# TTFT2.net
KiCad netlist of a schematic drawn in Altium Designer
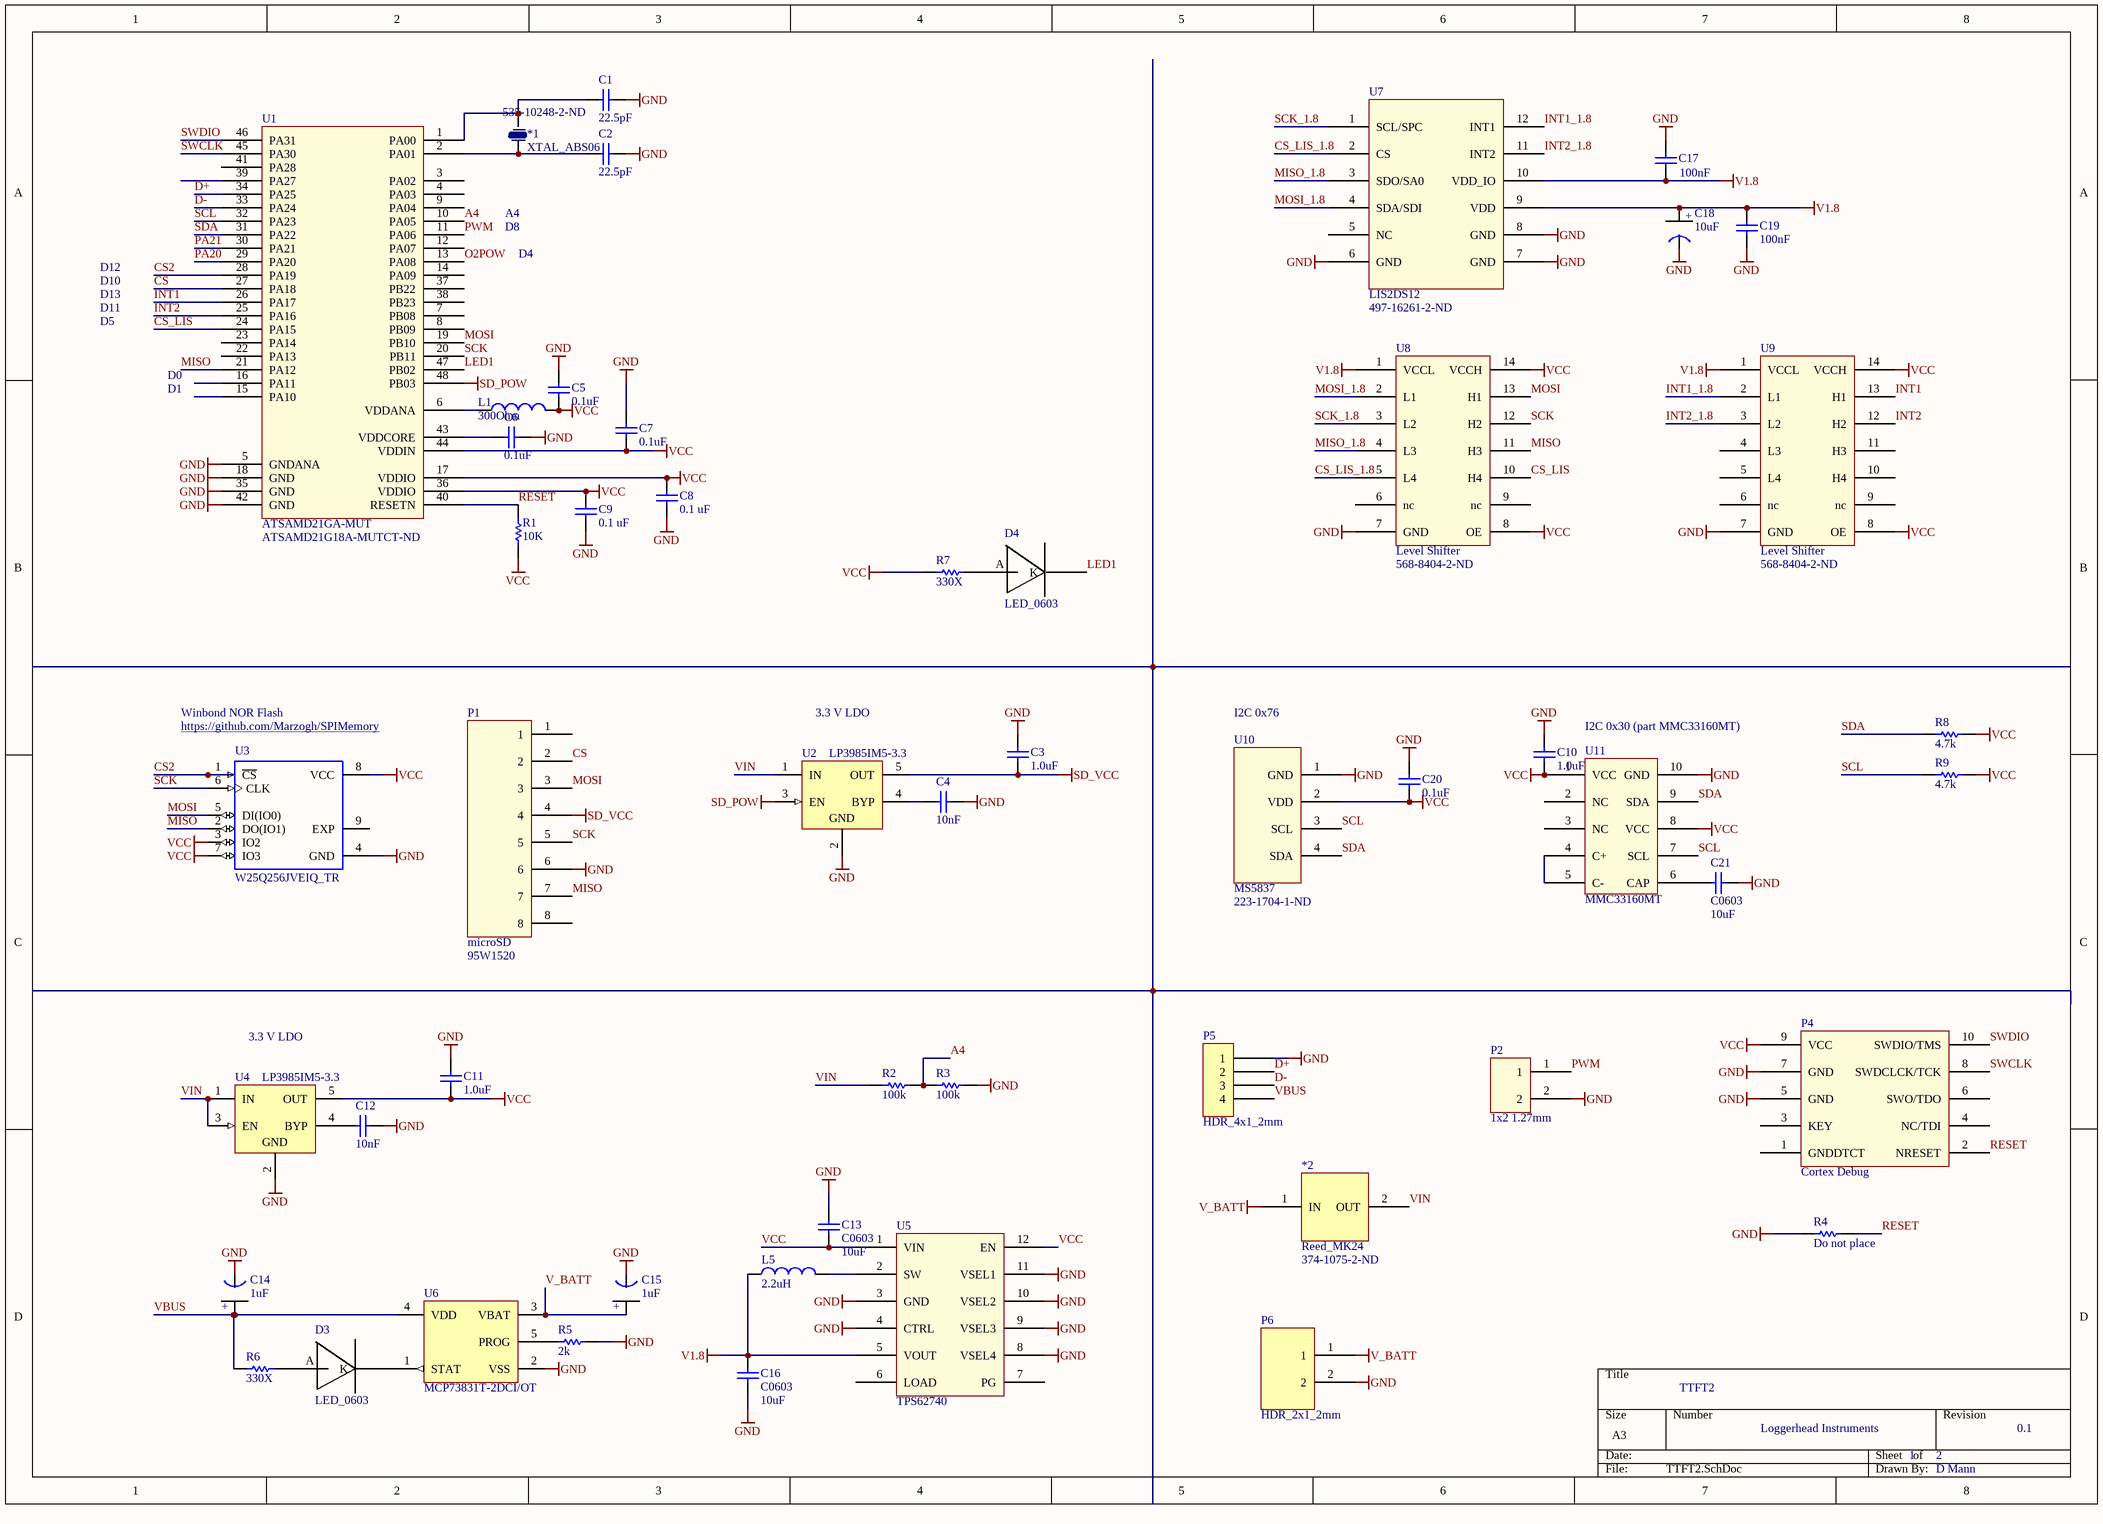
[diagram p0: TTFT2.SchDoc]

(export (version "E")
  (design (tool "Eeschema 10.0.6"))
  (components
    (comp (ref "*1")
      (value "XTAL_ABS06")
      (footprint "XTAL-ABS06")
      (fields (field (name "SUPPLIER PART NUMBER 1") "535-10248-2-ND"))
      (libsource (lib "Loggerhead") (part "XTAL_ABS06"))
    )
    (comp (ref "*2")
      (value "Reed_MK24")
      (footprint "Reed MK24-B-3")
      (fields (field (name "SUPPLIER PART NUMBER 1") "374-1075-2-ND"))
      (libsource (lib "Loggerhead") (part "Reed_MK24"))
    )
    (comp (ref "C1")
      (value "22.5pF")
      (footprint "0402")
      (description "Ceramic Chip Capacitor - Standard")
      (fields (field (name "PUBLISHER") "Altium Limited"))
      (libsource (lib "KEMET Chip Capacitor") (part "C0402"))
    )
    (comp (ref "C2")
      (value "22.5pF")
      (footprint "0402")
      (description "Ceramic Chip Capacitor - Standard")
      (fields (field (name "PUBLISHER") "Altium Limited"))
      (libsource (lib "KEMET Chip Capacitor") (part "C0402"))
    )
    (comp (ref "C3")
      (value "1.0uF")
      (footprint "0402")
      (description "Ceramic Chip Capacitor - Standard")
      (fields (field (name "PUBLISHER") "Altium Limited"))
      (libsource (lib "KEMET Chip Capacitor") (part "C0402"))
    )
    (comp (ref "C4")
      (value "10nF")
      (footprint "0402")
      (description "Ceramic Chip Capacitor - Standard")
      (fields (field (name "PUBLISHER") "Altium Limited"))
      (libsource (lib "KEMET Chip Capacitor") (part "C0402"))
    )
    (comp (ref "C5")
      (value "0.1uF")
      (footprint "0402")
      (description "Ceramic Chip Capacitor - Standard")
      (fields (field (name "PUBLISHER") "Altium Limited"))
      (libsource (lib "KEMET Chip Capacitor") (part "C0402"))
    )
    (comp (ref "C6")
      (value "0.1uF")
      (footprint "0402")
      (description "Ceramic Chip Capacitor - Standard")
      (fields (field (name "PUBLISHER") "Altium Limited"))
      (libsource (lib "KEMET Chip Capacitor") (part "C0402"))
    )
    (comp (ref "C7")
      (value "0.1uF")
      (footprint "0402")
      (description "Ceramic Chip Capacitor - Standard")
      (fields (field (name "PUBLISHER") "Altium Limited"))
      (libsource (lib "KEMET Chip Capacitor") (part "C0402"))
    )
    (comp (ref "C8")
      (value "0.1 uF")
      (footprint "0402")
      (description "Ceramic Chip Capacitor - Standard")
      (fields (field (name "PUBLISHER") "Altium Limited"))
      (libsource (lib "KEMET Chip Capacitor") (part "C0402"))
    )
    (comp (ref "C9")
      (value "0.1 uF")
      (footprint "0402")
      (description "Ceramic Chip Capacitor - Standard")
      (fields (field (name "PUBLISHER") "Altium Limited"))
      (libsource (lib "KEMET Chip Capacitor") (part "C0402"))
    )
    (comp (ref "C10")
      (value "1.0uF")
      (footprint "0402")
      (description "Ceramic Chip Capacitor - Standard")
      (fields (field (name "PUBLISHER") "Altium Limited"))
      (libsource (lib "KEMET Chip Capacitor") (part "C0402"))
    )
    (comp (ref "C11")
      (value "1.0uF")
      (footprint "0402")
      (description "Ceramic Chip Capacitor - Standard")
      (fields (field (name "PUBLISHER") "Altium Limited"))
      (libsource (lib "KEMET Chip Capacitor") (part "C0402"))
    )
    (comp (ref "C12")
      (value "10nF")
      (footprint "0402")
      (description "Ceramic Chip Capacitor - Standard")
      (fields (field (name "PUBLISHER") "Altium Limited"))
      (libsource (lib "KEMET Chip Capacitor") (part "C0402"))
    )
    (comp (ref "C13")
      (value "C0603")
      (footprint "0603")
      (description "Ceramic Chip Capacitor - Standard")
      (fields (field (name "ALTIUM_VALUE") "10uF") (field (name "PUBLISHER") "Altium Limited"))
      (libsource (lib "KEMET Chip Capacitor") (part "C0603"))
    )
    (comp (ref "C14") (value "1uF") (footprint "Tant0805") (libsource (lib "Loggerhead") (part "Tant0805")))
    (comp (ref "C15") (value "1uF") (footprint "Tant0805") (libsource (lib "Loggerhead") (part "Tant0805")))
    (comp (ref "C16")
      (value "C0603")
      (footprint "0603")
      (description "Ceramic Chip Capacitor - Standard")
      (fields (field (name "ALTIUM_VALUE") "10uF") (field (name "PUBLISHER") "Altium Limited"))
      (libsource (lib "KEMET Chip Capacitor") (part "C0603"))
    )
    (comp (ref "C17")
      (value "100nF")
      (footprint "0402")
      (description "Ceramic Chip Capacitor - Standard")
      (fields (field (name "PUBLISHER") "Altium Limited"))
      (libsource (lib "KEMET Chip Capacitor") (part "C0402"))
    )
    (comp (ref "C18") (value "10uF") (footprint "Tant0805") (libsource (lib "Loggerhead") (part "Tant0805")))
    (comp (ref "C19")
      (value "100nF")
      (footprint "0402")
      (description "Ceramic Chip Capacitor - Standard")
      (fields (field (name "PUBLISHER") "Altium Limited"))
      (libsource (lib "KEMET Chip Capacitor") (part "C0402"))
    )
    (comp (ref "C20")
      (value "0.1uF")
      (footprint "0402")
      (description "Ceramic Chip Capacitor - Standard")
      (fields (field (name "PUBLISHER") "Altium Limited"))
      (libsource (lib "KEMET Chip Capacitor") (part "C0402"))
    )
    (comp (ref "C21")
      (value "C0603")
      (footprint "0603")
      (description "Ceramic Chip Capacitor - Standard")
      (fields (field (name "ALTIUM_VALUE") "10uF") (field (name "PUBLISHER") "Altium Limited"))
      (libsource (lib "KEMET Chip Capacitor") (part "C0603"))
    )
    (comp (ref "D3")
      (value "LED_0603")
      (footprint "Diode0603")
      (libsource (lib "Loggerhead") (part "LED_0603"))
    )
    (comp (ref "D4")
      (value "LED_0603")
      (footprint "Diode0603")
      (libsource (lib "Loggerhead") (part "LED_0603"))
    )
    (comp (ref "L1")
      (value "300Ohm")
      (footprint "0805 (M2125) Ferrite")
      (description "Ferrite 25mOhm@DC,  60 Ohm@100MHz")
      (fields
        (field (name "CREATOR AND DATE") "Design Engineer's Name")
        (field (name "FOOTPRINT VERIFIED BY") "*")
        (field (name "SCHEMATIC VERIFIED BY") "*")
        (field (name "VENDOR INFO VERIFIED BY") "*")
      )
      (libsource (lib "Flanery") (part "Ferrite 0805(M2125) 3A"))
    )
    (comp (ref "L5")
      (value "2.2uH")
      (footprint "Inductor KLZ1608AHR")
      (libsource (lib "Loggerhead") (part "Inductor KLZ1608"))
    )
    (comp (ref "P1")
      (value "microSD")
      (footprint "Molex microSD")
      (fields (field (name "SUPPLIER PART NUMBER 1") "95W1520"))
      (libsource (lib "Loggerhead") (part "microSD Molex tiny"))
    )
    (comp (ref "P2")
      (value "1x2 1.27mm")
      (footprint "Header1x2 1.27mm")
      (libsource (lib "Loggerhead") (part "Header 1x2 1.27mm"))
    )
    (comp (ref "P4")
      (value "Cortex Debug")
      (footprint "Header_2x5_50mil")
      (libsource (lib "Loggerhead") (part "CortexDebug"))
    )
    (comp (ref "P5")
      (value "HDR_4x1_2mm")
      (footprint "Hdr_4x1_2mm")
      (libsource (lib "Loggerhead") (part "HDR_4x1_2mm"))
    )
    (comp (ref "P6")
      (value "HDR_2x1_2mm")
      (footprint "HDR_2x1_2mm")
      (libsource (lib "Loggerhead") (part "HDR_2x1_2mm"))
    )
    (comp (ref "R1")
      (value "10K")
      (footprint "3-0603")
      (fields (field (name "PUBLISHER") "Altium Limited"))
      (libsource (lib "Panasonic Resistor") (part "ERJ3RK"))
    )
    (comp (ref "R2")
      (value "100k")
      (footprint "3-0603")
      (fields (field (name "PUBLISHER") "Altium Limited"))
      (libsource (lib "Panasonic Resistor") (part "ERJ3RK"))
    )
    (comp (ref "R3")
      (value "100k")
      (footprint "3-0603")
      (fields (field (name "PUBLISHER") "Altium Limited"))
      (libsource (lib "Panasonic Resistor") (part "ERJ3RK"))
    )
    (comp (ref "R4")
      (value "Do not place")
      (footprint "3-0603")
      (fields (field (name "PUBLISHER") "Altium Limited"))
      (libsource (lib "Panasonic Resistor") (part "ERJ3RK"))
    )
    (comp (ref "R5")
      (value "2k")
      (footprint "3-0603")
      (fields (field (name "PUBLISHER") "Altium Limited"))
      (libsource (lib "Panasonic Resistor") (part "ERJ3RK"))
    )
    (comp (ref "R6")
      (value "330X")
      (footprint "3-0603")
      (fields (field (name "PUBLISHER") "Altium Limited"))
      (libsource (lib "Panasonic Resistor") (part "ERJ3RK"))
    )
    (comp (ref "R7")
      (value "330X")
      (footprint "3-0603")
      (fields (field (name "PUBLISHER") "Altium Limited"))
      (libsource (lib "Panasonic Resistor") (part "ERJ3RK"))
    )
    (comp (ref "R8")
      (value "4.7k")
      (footprint "3-0603")
      (fields (field (name "PUBLISHER") "Altium Limited"))
      (libsource (lib "Panasonic Resistor") (part "ERJ3RK"))
    )
    (comp (ref "R9")
      (value "4.7k")
      (footprint "3-0603")
      (fields (field (name "PUBLISHER") "Altium Limited"))
      (libsource (lib "Panasonic Resistor") (part "ERJ3RK"))
    )
    (comp (ref "U1")
      (value "ATSAMD21GA-MUT")
      (footprint "QFN127P600-8N")
      (fields (field (name "SUPPLIER PART NUMBER 1") "ATSAMD21G18A-MUTCT-ND"))
      (libsource (lib "Loggerhead") (part "ATSAMD21G18"))
    )
    (comp (ref "U2")
      (value "LP3985IM5-3.3")
      (footprint "MF05A_N")
      (description "Micropower, 150mA Low-Noise Ultra Low-Dropout CMOS Voltage Regulator, 5-pin SOT-23")
      (fields
        (field (name "MANUFACTURER") "National Semiconductor")
        (field (name "PUBLISHER") "Altium Limited")
      )
      (libsource (lib "NSC LDO") (part "LP3985IM5-3.3"))
    )
    (comp (ref "U3")
      (value "W25Q256JVEIQ_TR")
      (footprint "*SON127P800X600X80-9N")
      (description "Ic Flash 256mbit 104mhz 8wson")
      (fields (field (name "MF") "Winbond") (field (name "MP") "W25Q256JVEIQ TR"))
      (libsource (lib "W25Q256JVEIQ_TR") (part "W25Q256JVEIQ_TR"))
    )
    (comp (ref "U4")
      (value "LP3985IM5-3.3")
      (footprint "MF05A_N")
      (description "Micropower, 150mA Low-Noise Ultra Low-Dropout CMOS Voltage Regulator, 5-pin SOT-23")
      (fields
        (field (name "MANUFACTURER") "National Semiconductor")
        (field (name "PUBLISHER") "Altium Limited")
      )
      (libsource (lib "NSC LDO") (part "LP3985IM5-3.3"))
    )
    (comp (ref "U5")
      (value "TPS62740")
      (footprint "TPS6274x")
      (libsource (lib "Loggerhead") (part "TPS6274x"))
    )
    (comp (ref "U6")
      (value "MCP73831T-2DCI/OT")
      (footprint "SOT-23-OT5_N")
      (libsource (lib "Microchip Power Management Battery Management") (part "MCP73831T-2DCI/OT"))
    )
    (comp (ref "U7")
      (value "LIS2DS12")
      (footprint "LGA-12")
      (fields (field (name "SUPPLIER PART NUMBER 1") "497-16261-2-ND"))
      (libsource (lib "Loggerhead") (part "LIS2DS12"))
    )
    (comp (ref "U8")
      (value "Level Shifter")
      (footprint "DHVQFN14")
      (description "Voltage level translator")
      (fields (field (name "SUPPLIER PART NUMBER 1") "568-8404-2-ND"))
      (libsource (lib "Loggerhead") (part "NTB0104"))
    )
    (comp (ref "U9")
      (value "Level Shifter")
      (footprint "DHVQFN14")
      (description "Voltage level translator")
      (fields (field (name "SUPPLIER PART NUMBER 1") "568-8404-2-ND"))
      (libsource (lib "Loggerhead") (part "NTB0104"))
    )
    (comp (ref "U10")
      (value "MS5837")
      (footprint "MS5837")
      (description "Pressure/Temp")
      (fields (field (name "SUPPLIER PART NUMBER 1") "223-1704-1-ND"))
      (libsource (lib "Loggerhead") (part "MS5837"))
    )
    (comp (ref "U11")
      (value "MMC33160MT")
      (footprint "MMC33160MT")
      (libsource (lib "Loggerhead") (part "MMC33160MT"))
    )
  )
  (nets
    (net (code "1") (name "/A4") (class "Default")
      (node (ref "R2") (pin "1") (pinfunction "1_1") (pintype "passive"))
      (node (ref "R3") (pin "2") (pinfunction "2_2") (pintype "passive"))
      (node (ref "U1") (pin "10") (pinfunction "PA05_10") (pintype "passive"))
    )
    (net (code "2") (name "/CS") (class "Default")
      (node (ref "P1") (pin "2") (pinfunction "2_2") (pintype "passive"))
      (node (ref "U1") (pin "27") (pinfunction "PA18_27") (pintype "passive"))
    )
    (net (code "3") (name "/CS2") (class "Default")
      (node (ref "U1") (pin "28") (pinfunction "PA19_28") (pintype "passive"))
      (node (ref "U3") (pin "1") (pinfunction "~{CS}_1") (pintype "input"))
    )
    (net (code "4") (name "/CS_LIS") (class "Default")
      (node (ref "U1") (pin "24") (pinfunction "PA15_24") (pintype "passive"))
      (node (ref "U8") (pin "10") (pinfunction "H4_10") (pintype "passive"))
    )
    (net (code "5") (name "/CS_LIS_1.8") (class "Default")
      (node (ref "U7") (pin "2") (pinfunction "CS_2") (pintype "passive"))
      (node (ref "U8") (pin "5") (pinfunction "L4_5") (pintype "passive"))
    )
    (net (code "6") (name "/D+") (class "Default")
      (node (ref "P5") (pin "2") (pinfunction "2_2") (pintype "passive"))
      (node (ref "U1") (pin "34") (pinfunction "PA25_34") (pintype "passive"))
    )
    (net (code "7") (name "/D-") (class "Default")
      (node (ref "P5") (pin "3") (pinfunction "3_3") (pintype "passive"))
      (node (ref "U1") (pin "33") (pinfunction "PA24_33") (pintype "passive"))
    )
    (net (code "8") (name "/INT1") (class "Default")
      (node (ref "U1") (pin "26") (pinfunction "PA17_26") (pintype "passive"))
      (node (ref "U9") (pin "13") (pinfunction "H1_13") (pintype "passive"))
    )
    (net (code "9") (name "/INT1_1.8") (class "Default")
      (node (ref "U7") (pin "12") (pinfunction "INT1_12") (pintype "passive"))
      (node (ref "U9") (pin "2") (pinfunction "L1_2") (pintype "passive"))
    )
    (net (code "10") (name "/INT2") (class "Default")
      (node (ref "U1") (pin "25") (pinfunction "PA16_25") (pintype "passive"))
      (node (ref "U9") (pin "12") (pinfunction "H2_12") (pintype "passive"))
    )
    (net (code "11") (name "/INT2_1.8") (class "Default")
      (node (ref "U7") (pin "11") (pinfunction "INT2_11") (pintype "passive"))
      (node (ref "U9") (pin "3") (pinfunction "L2_3") (pintype "passive"))
    )
    (net (code "12") (name "/LED1") (class "Default")
      (node (ref "D4") (pin "K") (pinfunction "K_K") (pintype "passive"))
      (node (ref "U1") (pin "47") (pinfunction "PB02_47") (pintype "passive"))
    )
    (net (code "13") (name "/MISO") (class "Default")
      (node (ref "P1") (pin "7") (pinfunction "7_7") (pintype "passive"))
      (node (ref "U1") (pin "21") (pinfunction "PA12_21") (pintype "passive"))
      (node (ref "U3") (pin "2") (pinfunction "DO(IO1)_2") (pintype "bidirectional"))
      (node (ref "U8") (pin "11") (pinfunction "H3_11") (pintype "passive"))
    )
    (net (code "14") (name "/MISO_1.8") (class "Default")
      (node (ref "U7") (pin "3") (pinfunction "SDO/SA0_3") (pintype "passive"))
      (node (ref "U8") (pin "4") (pinfunction "L3_4") (pintype "passive"))
    )
    (net (code "15") (name "/MOSI") (class "Default")
      (node (ref "P1") (pin "3") (pinfunction "3_3") (pintype "passive"))
      (node (ref "U1") (pin "19") (pinfunction "PB10_19") (pintype "passive"))
      (node (ref "U3") (pin "5") (pinfunction "DI(IO0)_5") (pintype "bidirectional"))
      (node (ref "U8") (pin "13") (pinfunction "H1_13") (pintype "passive"))
    )
    (net (code "16") (name "/MOSI_1.8") (class "Default")
      (node (ref "U7") (pin "4") (pinfunction "SDA/SDI_4") (pintype "passive"))
      (node (ref "U8") (pin "2") (pinfunction "L1_2") (pintype "passive"))
    )
    (net (code "17") (name "/O2POW") (class "Default")
      (node (ref "U1") (pin "13") (pinfunction "PA08_13") (pintype "passive"))
    )
    (net (code "18") (name "/PA20") (class "Default")
      (node (ref "U1") (pin "29") (pinfunction "PA20_29") (pintype "passive"))
    )
    (net (code "19") (name "/PA21") (class "Default")
      (node (ref "U1") (pin "30") (pinfunction "PA21_30") (pintype "passive"))
    )
    (net (code "20") (name "/PWM") (class "Default")
      (node (ref "P2") (pin "1") (pinfunction "1_1") (pintype "passive"))
      (node (ref "U1") (pin "11") (pinfunction "PA06_11") (pintype "passive"))
    )
    (net (code "21") (name "/RESET") (class "Default")
      (node (ref "P4") (pin "2") (pinfunction "NRESET_2") (pintype "passive"))
      (node (ref "R1") (pin "2") (pinfunction "2_2") (pintype "passive"))
      (node (ref "R4") (pin "1") (pinfunction "1_1") (pintype "passive"))
      (node (ref "U1") (pin "40") (pinfunction "RESETN_40") (pintype "passive"))
    )
    (net (code "22") (name "/SCK") (class "Default")
      (node (ref "P1") (pin "5") (pinfunction "5_5") (pintype "passive"))
      (node (ref "U1") (pin "20") (pinfunction "PB11_20") (pintype "passive"))
      (node (ref "U3") (pin "6") (pinfunction "CLK_6") (pintype "input"))
      (node (ref "U8") (pin "12") (pinfunction "H2_12") (pintype "passive"))
    )
    (net (code "23") (name "/SCK_1.8") (class "Default")
      (node (ref "U7") (pin "1") (pinfunction "SCL/SPC_1") (pintype "passive"))
      (node (ref "U8") (pin "3") (pinfunction "L2_3") (pintype "passive"))
    )
    (net (code "24") (name "/SCL") (class "Default")
      (node (ref "R9") (pin "1") (pinfunction "1_1") (pintype "passive"))
      (node (ref "U1") (pin "32") (pinfunction "PA23_32") (pintype "passive"))
      (node (ref "U10") (pin "3") (pinfunction "SCL_3") (pintype "passive"))
      (node (ref "U11") (pin "7") (pinfunction "SCL_7") (pintype "passive"))
    )
    (net (code "25") (name "/SDA") (class "Default")
      (node (ref "R8") (pin "2") (pinfunction "2_2") (pintype "passive"))
      (node (ref "U1") (pin "31") (pinfunction "PA22_31") (pintype "passive"))
      (node (ref "U10") (pin "4") (pinfunction "SDA_4") (pintype "passive"))
      (node (ref "U11") (pin "9") (pinfunction "SDA_9") (pintype "passive"))
    )
    (net (code "26") (name "/SWCLK") (class "Default")
      (node (ref "P4") (pin "8") (pinfunction "SWDCLCK/TCK_8") (pintype "passive"))
      (node (ref "U1") (pin "45") (pinfunction "PA30_45") (pintype "passive"))
    )
    (net (code "27") (name "/SWDIO") (class "Default")
      (node (ref "P4") (pin "10") (pinfunction "SWDIO/TMS_10") (pintype "passive"))
      (node (ref "U1") (pin "46") (pinfunction "PA31_46") (pintype "passive"))
    )
    (net (code "28") (name "/VBUS") (class "Default")
      (node (ref "C14") (pin "2") (pinfunction "+_2") (pintype "passive"))
      (node (ref "P5") (pin "4") (pinfunction "4_4") (pintype "passive"))
      (node (ref "R6") (pin "1") (pinfunction "1_1") (pintype "passive"))
      (node (ref "U6") (pin "4") (pinfunction "VDD_4") (pintype "power_in"))
    )
    (net (code "29") (name "/VIN") (class "Default")
      (node (ref "*2") (pin "2") (pinfunction "OUT_2") (pintype "passive"))
      (node (ref "R2") (pin "2") (pinfunction "2_2") (pintype "passive"))
      (node (ref "U2") (pin "1") (pinfunction "IN_1") (pintype "power_in"))
      (node (ref "U4") (pin "1") (pinfunction "IN_1") (pintype "power_in"))
      (node (ref "U4") (pin "3") (pinfunction "EN_3") (pintype "input"))
    )
    (net (code "30") (name "GND") (class "Default")
      (node (ref "C1") (pin "1") (pinfunction "1_1") (pintype "passive"))
      (node (ref "C10") (pin "2") (pinfunction "2_2") (pintype "passive"))
      (node (ref "C11") (pin "2") (pinfunction "2_2") (pintype "passive"))
      (node (ref "C12") (pin "1") (pinfunction "1_1") (pintype "passive"))
      (node (ref "C13") (pin "2") (pinfunction "2_2") (pintype "passive"))
      (node (ref "C14") (pin "1") (pinfunction "GND_1") (pintype "passive"))
      (node (ref "C15") (pin "1") (pinfunction "GND_1") (pintype "passive"))
      (node (ref "C16") (pin "1") (pinfunction "1_1") (pintype "passive"))
      (node (ref "C17") (pin "2") (pinfunction "2_2") (pintype "passive"))
      (node (ref "C18") (pin "1") (pinfunction "GND_1") (pintype "passive"))
      (node (ref "C19") (pin "2") (pinfunction "2_2") (pintype "passive"))
      (node (ref "C2") (pin "1") (pinfunction "1_1") (pintype "passive"))
      (node (ref "C20") (pin "2") (pinfunction "2_2") (pintype "passive"))
      (node (ref "C21") (pin "1") (pinfunction "1_1") (pintype "passive"))
      (node (ref "C3") (pin "2") (pinfunction "2_2") (pintype "passive"))
      (node (ref "C4") (pin "1") (pinfunction "1_1") (pintype "passive"))
      (node (ref "C5") (pin "2") (pinfunction "2_2") (pintype "passive"))
      (node (ref "C6") (pin "2") (pinfunction "2_2") (pintype "passive"))
      (node (ref "C7") (pin "2") (pinfunction "2_2") (pintype "passive"))
      (node (ref "C8") (pin "2") (pinfunction "2_2") (pintype "passive"))
      (node (ref "C9") (pin "2") (pinfunction "2_2") (pintype "passive"))
      (node (ref "P1") (pin "6") (pinfunction "6_6") (pintype "passive"))
      (node (ref "P2") (pin "2") (pinfunction "2_2") (pintype "passive"))
      (node (ref "P4") (pin "5") (pinfunction "GND_5") (pintype "passive"))
      (node (ref "P4") (pin "7") (pinfunction "GND_7") (pintype "passive"))
      (node (ref "P5") (pin "1") (pinfunction "1_1") (pintype "passive"))
      (node (ref "P6") (pin "2") (pinfunction "2_2") (pintype "passive"))
      (node (ref "R3") (pin "1") (pinfunction "1_1") (pintype "passive"))
      (node (ref "R4") (pin "2") (pinfunction "2_2") (pintype "passive"))
      (node (ref "R5") (pin "1") (pinfunction "1_1") (pintype "passive"))
      (node (ref "U1") (pin "18") (pinfunction "GND_18") (pintype "passive"))
      (node (ref "U1") (pin "35") (pinfunction "GND_35") (pintype "passive"))
      (node (ref "U1") (pin "42") (pinfunction "GND_42") (pintype "passive"))
      (node (ref "U1") (pin "5") (pinfunction "GNDANA_5") (pintype "passive"))
      (node (ref "U10") (pin "1") (pinfunction "GND_1") (pintype "passive"))
      (node (ref "U11") (pin "10") (pinfunction "GND_10") (pintype "passive"))
      (node (ref "U2") (pin "2") (pinfunction "GND_2") (pintype "power_in"))
      (node (ref "U3") (pin "4") (pinfunction "GND_4") (pintype "power_in"))
      (node (ref "U4") (pin "2") (pinfunction "GND_2") (pintype "power_in"))
      (node (ref "U5") (pin "10") (pinfunction "VSEL2_10") (pintype "passive"))
      (node (ref "U5") (pin "11") (pinfunction "VSEL1_11") (pintype "passive"))
      (node (ref "U5") (pin "3") (pinfunction "GND_3") (pintype "passive"))
      (node (ref "U5") (pin "4") (pinfunction "CTRL_4") (pintype "passive"))
      (node (ref "U5") (pin "8") (pinfunction "VSEL4_8") (pintype "passive"))
      (node (ref "U5") (pin "9") (pinfunction "VSEL3_9") (pintype "passive"))
      (node (ref "U6") (pin "2") (pinfunction "VSS_2") (pintype "power_in"))
      (node (ref "U7") (pin "6") (pinfunction "GND_6") (pintype "passive"))
      (node (ref "U7") (pin "7") (pinfunction "GND_7") (pintype "passive"))
      (node (ref "U7") (pin "8") (pinfunction "GND_8") (pintype "passive"))
      (node (ref "U8") (pin "7") (pinfunction "GND_7") (pintype "passive"))
      (node (ref "U9") (pin "7") (pinfunction "GND_7") (pintype "passive"))
    )
    (net (code "31") (name "Net-(D3-PadA)") (class "Default")
      (node (ref "D3") (pin "A") (pinfunction "A_A") (pintype "passive"))
      (node (ref "R6") (pin "2") (pinfunction "2_2") (pintype "passive"))
    )
    (net (code "32") (name "Net-(D4-PadA)") (class "Default")
      (node (ref "D4") (pin "A") (pinfunction "A_A") (pintype "passive"))
      (node (ref "R7") (pin "2") (pinfunction "2_2") (pintype "passive"))
    )
    (net (code "33") (name "Net-(U1-PA00)") (class "Default")
      (node (ref "*1") (pin "2") (pinfunction "2_2") (pintype "passive"))
      (node (ref "C1") (pin "2") (pinfunction "2_2") (pintype "passive"))
      (node (ref "U1") (pin "1") (pinfunction "PA00_1") (pintype "passive"))
    )
    (net (code "34") (name "Net-(U1-PA01)") (class "Default")
      (node (ref "*1") (pin "1") (pinfunction "1_1") (pintype "passive"))
      (node (ref "C2") (pin "2") (pinfunction "2_2") (pintype "passive"))
      (node (ref "U1") (pin "2") (pinfunction "PA01_2") (pintype "passive"))
    )
    (net (code "35") (name "Net-(U1-VDDANA)") (class "Default")
      (node (ref "L1") (pin "1") (pinfunction "1_1") (pintype "passive"))
      (node (ref "U1") (pin "6") (pinfunction "VDDANA_6") (pintype "passive"))
    )
    (net (code "36") (name "Net-(U1-VDDCORE)") (class "Default")
      (node (ref "C6") (pin "1") (pinfunction "1_1") (pintype "passive"))
      (node (ref "U1") (pin "43") (pinfunction "VDDCORE_43") (pintype "passive"))
    )
    (net (code "37") (name "Net-(U2-BYP)") (class "Default")
      (node (ref "C4") (pin "2") (pinfunction "2_2") (pintype "passive"))
      (node (ref "U2") (pin "4") (pinfunction "BYP_4") (pintype "passive"))
    )
    (net (code "38") (name "Net-(U4-BYP)") (class "Default")
      (node (ref "C12") (pin "2") (pinfunction "2_2") (pintype "passive"))
      (node (ref "U4") (pin "4") (pinfunction "BYP_4") (pintype "passive"))
    )
    (net (code "39") (name "Net-(U5-SW)") (class "Default")
      (node (ref "L5") (pin "2") (pinfunction "2_2") (pintype "passive"))
      (node (ref "U5") (pin "2") (pinfunction "SW_2") (pintype "passive"))
    )
    (net (code "40") (name "Net-(U6-PROG)") (class "Default")
      (node (ref "R5") (pin "2") (pinfunction "2_2") (pintype "passive"))
      (node (ref "U6") (pin "5") (pinfunction "PROG_5") (pintype "passive"))
    )
    (net (code "41") (name "Net-(U6-STAT)") (class "Default")
      (node (ref "D3") (pin "K") (pinfunction "K_K") (pintype "passive"))
      (node (ref "U6") (pin "1") (pinfunction "STAT_1") (pintype "output"))
    )
    (net (code "42") (name "Net-(U11-C+)") (class "Default")
      (node (ref "U11") (pin "4") (pinfunction "C+_4") (pintype "passive"))
      (node (ref "U11") (pin "5") (pinfunction "C-_5") (pintype "passive"))
    )
    (net (code "43") (name "Net-(U11-CAP)") (class "Default")
      (node (ref "C21") (pin "2") (pinfunction "2_2") (pintype "passive"))
      (node (ref "U11") (pin "6") (pinfunction "CAP_6") (pintype "passive"))
    )
    (net (code "44") (name "SD_POW") (class "Default")
      (node (ref "U1") (pin "48") (pinfunction "PB03_48") (pintype "passive"))
      (node (ref "U2") (pin "3") (pinfunction "EN_3") (pintype "input"))
    )
    (net (code "45") (name "SD_VCC") (class "Default")
      (node (ref "C3") (pin "1") (pinfunction "1_1") (pintype "passive"))
      (node (ref "P1") (pin "4") (pinfunction "4_4") (pintype "passive"))
      (node (ref "U2") (pin "5") (pinfunction "OUT_5") (pintype "power_in"))
    )
    (net (code "46") (name "V1.8") (class "Default")
      (node (ref "C16") (pin "2") (pinfunction "2_2") (pintype "passive"))
      (node (ref "C17") (pin "1") (pinfunction "1_1") (pintype "passive"))
      (node (ref "C18") (pin "2") (pinfunction "+_2") (pintype "passive"))
      (node (ref "C19") (pin "1") (pinfunction "1_1") (pintype "passive"))
      (node (ref "L5") (pin "1") (pinfunction "1_1") (pintype "passive"))
      (node (ref "U5") (pin "5") (pinfunction "VOUT_5") (pintype "passive"))
      (node (ref "U7") (pin "10") (pinfunction "VDD_IO_10") (pintype "passive"))
      (node (ref "U7") (pin "9") (pinfunction "VDD_9") (pintype "passive"))
      (node (ref "U8") (pin "1") (pinfunction "VCCL_1") (pintype "passive"))
      (node (ref "U9") (pin "1") (pinfunction "VCCL_1") (pintype "passive"))
    )
    (net (code "47") (name "VCC") (class "Default")
      (node (ref "C10") (pin "1") (pinfunction "1_1") (pintype "passive"))
      (node (ref "C11") (pin "1") (pinfunction "1_1") (pintype "passive"))
      (node (ref "C13") (pin "1") (pinfunction "1_1") (pintype "passive"))
      (node (ref "C20") (pin "1") (pinfunction "1_1") (pintype "passive"))
      (node (ref "C5") (pin "1") (pinfunction "1_1") (pintype "passive"))
      (node (ref "C7") (pin "1") (pinfunction "1_1") (pintype "passive"))
      (node (ref "C8") (pin "1") (pinfunction "1_1") (pintype "passive"))
      (node (ref "C9") (pin "1") (pinfunction "1_1") (pintype "passive"))
      (node (ref "L1") (pin "2") (pinfunction "2_2") (pintype "passive"))
      (node (ref "P4") (pin "9") (pinfunction "VCC_9") (pintype "passive"))
      (node (ref "R1") (pin "1") (pinfunction "1_1") (pintype "passive"))
      (node (ref "R7") (pin "1") (pinfunction "1_1") (pintype "passive"))
      (node (ref "R8") (pin "1") (pinfunction "1_1") (pintype "passive"))
      (node (ref "R9") (pin "2") (pinfunction "2_2") (pintype "passive"))
      (node (ref "U1") (pin "17") (pinfunction "VDDIO_17") (pintype "passive"))
      (node (ref "U1") (pin "36") (pinfunction "VDDIO_36") (pintype "passive"))
      (node (ref "U1") (pin "44") (pinfunction "VDDIN_44") (pintype "passive"))
      (node (ref "U10") (pin "2") (pinfunction "VDD_2") (pintype "passive"))
      (node (ref "U11") (pin "1") (pinfunction "VCC_1") (pintype "passive"))
      (node (ref "U11") (pin "8") (pinfunction "VCC_8") (pintype "passive"))
      (node (ref "U3") (pin "3") (pinfunction "IO2_3") (pintype "bidirectional"))
      (node (ref "U3") (pin "7") (pinfunction "IO3_7") (pintype "bidirectional"))
      (node (ref "U3") (pin "8") (pinfunction "VCC_8") (pintype "power_in"))
      (node (ref "U4") (pin "5") (pinfunction "OUT_5") (pintype "power_in"))
      (node (ref "U5") (pin "1") (pinfunction "VIN_1") (pintype "passive"))
      (node (ref "U5") (pin "12") (pinfunction "EN_12") (pintype "passive"))
      (node (ref "U8") (pin "14") (pinfunction "VCCH_14") (pintype "passive"))
      (node (ref "U8") (pin "8") (pinfunction "OE_8") (pintype "passive"))
      (node (ref "U9") (pin "14") (pinfunction "VCCH_14") (pintype "passive"))
      (node (ref "U9") (pin "8") (pinfunction "OE_8") (pintype "passive"))
    )
    (net (code "48") (name "V_BATT") (class "Default")
      (node (ref "*2") (pin "1") (pinfunction "IN_1") (pintype "passive"))
      (node (ref "C15") (pin "2") (pinfunction "+_2") (pintype "passive"))
      (node (ref "P6") (pin "1") (pinfunction "1_1") (pintype "passive"))
      (node (ref "U6") (pin "3") (pinfunction "VBAT_3") (pintype "power_in"))
    )
    (net (code "49") (name "unconnected-(P1-Pad1)") (class "Default")
      (node (ref "P1") (pin "1") (pinfunction "1_1") (pintype "passive"))
    )
    (net (code "50") (name "unconnected-(P1-Pad8)") (class "Default")
      (node (ref "P1") (pin "8") (pinfunction "8_8") (pintype "passive"))
    )
    (net (code "51") (name "unconnected-(P4-GNDDTCT-Pad1)") (class "Default")
      (node (ref "P4") (pin "1") (pinfunction "GNDDTCT_1") (pintype "passive"))
    )
    (net (code "52") (name "unconnected-(P4-KEY-Pad3)") (class "Default")
      (node (ref "P4") (pin "3") (pinfunction "KEY_3") (pintype "passive"))
    )
    (net (code "53") (name "unconnected-(P4-NC{slash}TDI-Pad4)") (class "Default")
      (node (ref "P4") (pin "4") (pinfunction "NC/TDI_4") (pintype "passive"))
    )
    (net (code "54") (name "unconnected-(P4-SWO{slash}TDO-Pad6)") (class "Default")
      (node (ref "P4") (pin "6") (pinfunction "SWO/TDO_6") (pintype "passive"))
    )
    (net (code "55") (name "unconnected-(U1-PA02-Pad3)") (class "Default")
      (node (ref "U1") (pin "3") (pinfunction "PA02_3") (pintype "passive"))
    )
    (net (code "56") (name "unconnected-(U1-PA03-Pad4)") (class "Default")
      (node (ref "U1") (pin "4") (pinfunction "PA03_4") (pintype "passive"))
    )
    (net (code "57") (name "unconnected-(U1-PA04-Pad9)") (class "Default")
      (node (ref "U1") (pin "9") (pinfunction "PA04_9") (pintype "passive"))
    )
    (net (code "58") (name "unconnected-(U1-PA07-Pad12)") (class "Default")
      (node (ref "U1") (pin "12") (pinfunction "PA07_12") (pintype "passive"))
    )
    (net (code "59") (name "unconnected-(U1-PA09-Pad14)") (class "Default")
      (node (ref "U1") (pin "14") (pinfunction "PA09_14") (pintype "passive"))
    )
    (net (code "60") (name "unconnected-(U1-PA10-Pad15)") (class "Default")
      (node (ref "U1") (pin "15") (pinfunction "PA10_15") (pintype "passive"))
    )
    (net (code "61") (name "unconnected-(U1-PA11-Pad16)") (class "Default")
      (node (ref "U1") (pin "16") (pinfunction "PA11_16") (pintype "passive"))
    )
    (net (code "62") (name "unconnected-(U1-PA13-Pad22)") (class "Default")
      (node (ref "U1") (pin "22") (pinfunction "PA13_22") (pintype "passive"))
    )
    (net (code "63") (name "unconnected-(U1-PA14-Pad23)") (class "Default")
      (node (ref "U1") (pin "23") (pinfunction "PA14_23") (pintype "passive"))
    )
    (net (code "64") (name "unconnected-(U1-PA27-Pad39)") (class "Default")
      (node (ref "U1") (pin "39") (pinfunction "PA27_39") (pintype "passive"))
    )
    (net (code "65") (name "unconnected-(U1-PA28-Pad41)") (class "Default")
      (node (ref "U1") (pin "41") (pinfunction "PA28_41") (pintype "passive"))
    )
    (net (code "66") (name "unconnected-(U1-PB08-Pad7)") (class "Default")
      (node (ref "U1") (pin "7") (pinfunction "PB08_7") (pintype "passive"))
    )
    (net (code "67") (name "unconnected-(U1-PB09-Pad8)") (class "Default")
      (node (ref "U1") (pin "8") (pinfunction "PB09_8") (pintype "passive"))
    )
    (net (code "68") (name "unconnected-(U1-PB22-Pad37)") (class "Default")
      (node (ref "U1") (pin "37") (pinfunction "PB22_37") (pintype "passive"))
    )
    (net (code "69") (name "unconnected-(U1-PB23-Pad38)") (class "Default")
      (node (ref "U1") (pin "38") (pinfunction "PB23_38") (pintype "passive"))
    )
    (net (code "70") (name "unconnected-(U3-EXP-Pad9)") (class "Default")
      (node (ref "U3") (pin "9") (pinfunction "EXP_9") (pintype "power_in"))
    )
    (net (code "71") (name "unconnected-(U5-LOAD-Pad6)") (class "Default")
      (node (ref "U5") (pin "6") (pinfunction "LOAD_6") (pintype "passive"))
    )
    (net (code "72") (name "unconnected-(U5-PG-Pad7)") (class "Default")
      (node (ref "U5") (pin "7") (pinfunction "PG_7") (pintype "passive"))
    )
    (net (code "73") (name "unconnected-(U7-NC-Pad5)") (class "Default")
      (node (ref "U7") (pin "5") (pinfunction "NC_5") (pintype "passive"))
    )
    (net (code "74") (name "unconnected-(U8-nc-Pad6)") (class "Default")
      (node (ref "U8") (pin "6") (pinfunction "nc_6") (pintype "passive"))
    )
    (net (code "75") (name "unconnected-(U8-nc-Pad9)") (class "Default")
      (node (ref "U8") (pin "9") (pinfunction "nc_9") (pintype "passive"))
    )
    (net (code "76") (name "unconnected-(U9-H3-Pad11)") (class "Default")
      (node (ref "U9") (pin "11") (pinfunction "H3_11") (pintype "passive"))
    )
    (net (code "77") (name "unconnected-(U9-H4-Pad10)") (class "Default")
      (node (ref "U9") (pin "10") (pinfunction "H4_10") (pintype "passive"))
    )
    (net (code "78") (name "unconnected-(U9-L3-Pad4)") (class "Default")
      (node (ref "U9") (pin "4") (pinfunction "L3_4") (pintype "passive"))
    )
    (net (code "79") (name "unconnected-(U9-L4-Pad5)") (class "Default")
      (node (ref "U9") (pin "5") (pinfunction "L4_5") (pintype "passive"))
    )
    (net (code "80") (name "unconnected-(U9-nc-Pad6)") (class "Default")
      (node (ref "U9") (pin "6") (pinfunction "nc_6") (pintype "passive"))
    )
    (net (code "81") (name "unconnected-(U9-nc-Pad9)") (class "Default")
      (node (ref "U9") (pin "9") (pinfunction "nc_9") (pintype "passive"))
    )
    (net (code "82") (name "unconnected-(U11-NC-Pad2)") (class "Default")
      (node (ref "U11") (pin "2") (pinfunction "NC_2") (pintype "passive"))
    )
    (net (code "83") (name "unconnected-(U11-NC-Pad3)") (class "Default")
      (node (ref "U11") (pin "3") (pinfunction "NC_3") (pintype "passive"))
    )
  )
)
